# main.net
KiCad netlist of a schematic drawn in Altium Designer
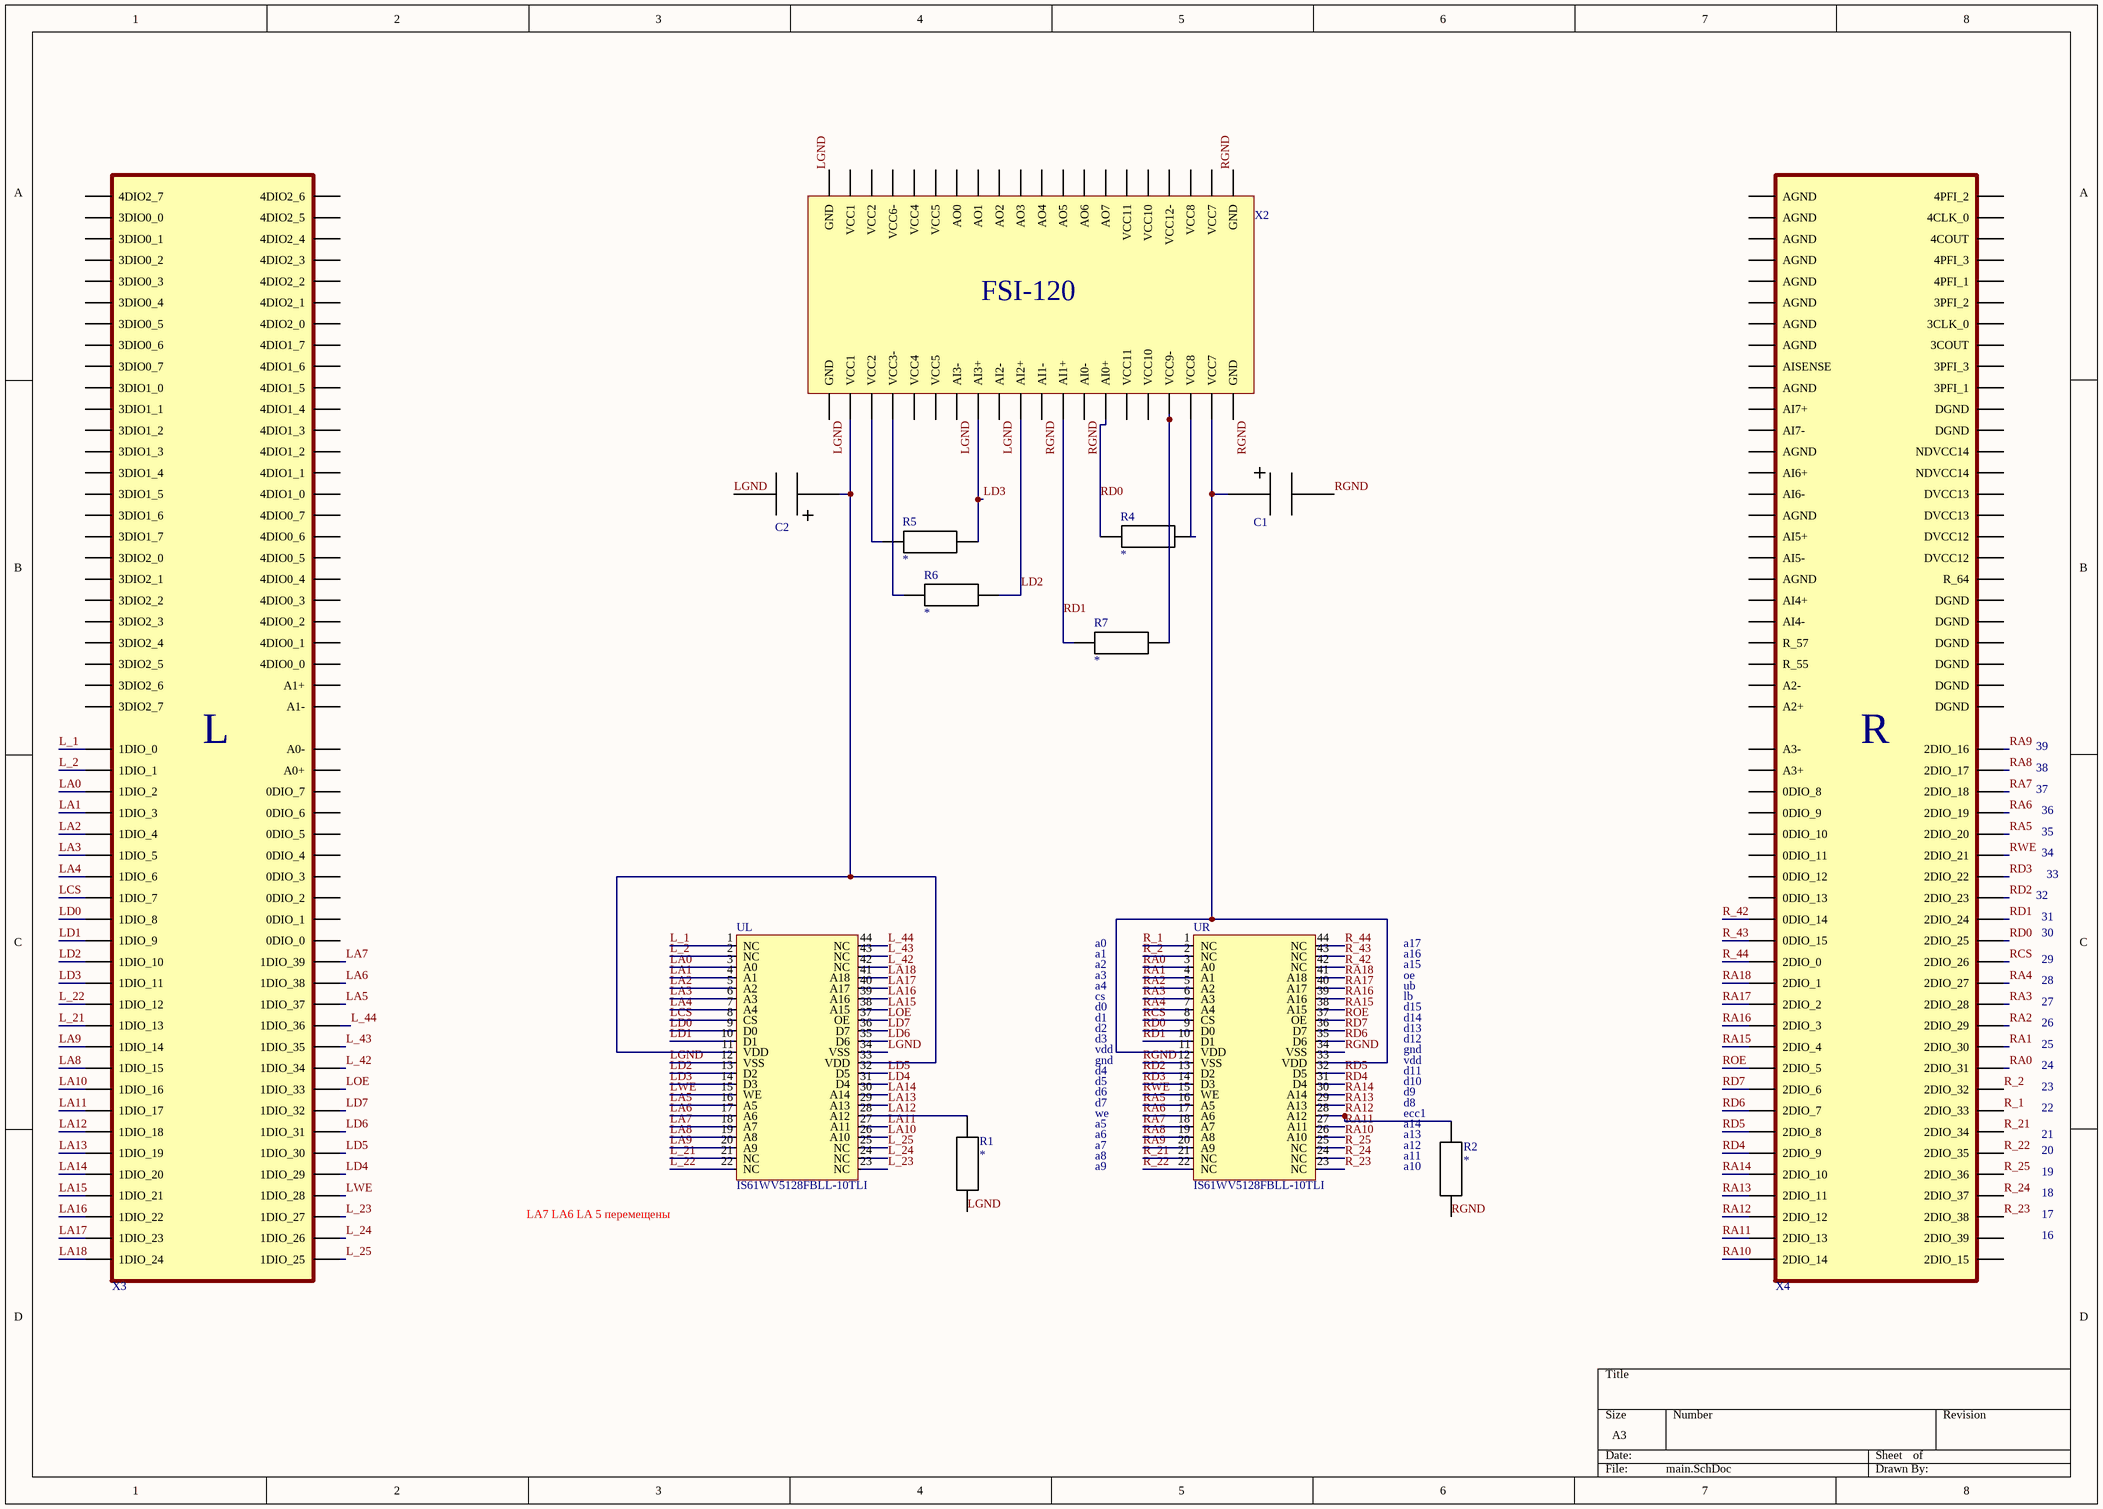
[diagram p0: main.SchDoc]

(export (version "E")
  (design (tool "Eeschema 10.0.6"))
  (components
    (comp (ref "C1")
      (value "C_Ta")
      (footprint "C_Ta")
      (description "tantalum capacitor")
      (libsource (lib "test_lib") (part "C_Ta"))
    )
    (comp (ref "C2")
      (value "C_Ta")
      (footprint "C_Ta")
      (description "tantalum capacitor")
      (libsource (lib "test_lib") (part "C_Ta"))
    )
    (comp (ref "R1")
      (value "*")
      (footprint "0805")
      (description "0805 resistor")
      (libsource (lib "test_lib") (part "R0805"))
    )
    (comp (ref "R2")
      (value "*")
      (footprint "0805")
      (description "0805 resistor")
      (libsource (lib "test_lib") (part "R0805"))
    )
    (comp (ref "R4")
      (value "*")
      (footprint "0805")
      (description "0805 resistor")
      (libsource (lib "test_lib") (part "R0805"))
    )
    (comp (ref "R5")
      (value "*")
      (footprint "0805")
      (description "0805 resistor")
      (libsource (lib "test_lib") (part "R0805"))
    )
    (comp (ref "R6")
      (value "*")
      (footprint "0805")
      (description "0805 resistor")
      (libsource (lib "test_lib") (part "R0805"))
    )
    (comp (ref "R7")
      (value "*")
      (footprint "0805")
      (description "0805 resistor")
      (libsource (lib "test_lib") (part "R0805"))
    )
    (comp (ref "UL")
      (value "IS61WV5128FBLL-10TLI")
      (footprint "TSOP (Type II)")
      (libsource (lib "test_lib") (part "IS61WV5128FBLL-10TLI"))
    )
    (comp (ref "UR")
      (value "IS61WV5128FBLL-10TLI")
      (footprint "TSOP (Type II)")
      (libsource (lib "test_lib") (part "IS61WV5128FBLL-10TLI"))
    )
    (comp (ref "X2") (value "FSI120") (footprint "FSI-120") (libsource (lib "test_lib") (part "FSI120")))
    (comp (ref "X3")
      (value "FSI-150-L")
      (footprint "FSI-150")
      (description "fsi 150 left")
      (libsource (lib "spels_lib") (part "FSI-150-L"))
    )
    (comp (ref "X4")
      (value "FSI-150-R")
      (footprint "FSI-150")
      (description "fsi 150 right")
      (libsource (lib "spels_lib") (part "FSI-150-R"))
    )
  )
  (nets
    (net (code "1") (name "/LA0") (class "Default")
      (node (ref "UL") (pin "3") (pinfunction "A0_3") (pintype "passive"))
      (node (ref "X3") (pin "R_45") (pinfunction "1DIO_2_R_45") (pintype "passive"))
    )
    (net (code "2") (name "/LA1") (class "Default")
      (node (ref "UL") (pin "4") (pinfunction "A1_4") (pintype "passive"))
      (node (ref "X3") (pin "R_43") (pinfunction "1DIO_3_R_43") (pintype "passive"))
    )
    (net (code "3") (name "/LA2") (class "Default")
      (node (ref "UL") (pin "5") (pinfunction "A2_5") (pintype "passive"))
      (node (ref "X3") (pin "R_41") (pinfunction "1DIO_4_R_41") (pintype "passive"))
    )
    (net (code "4") (name "/LA3") (class "Default")
      (node (ref "UL") (pin "6") (pinfunction "A3_6") (pintype "passive"))
      (node (ref "X3") (pin "R_39") (pinfunction "1DIO_5_R_39") (pintype "passive"))
    )
    (net (code "5") (name "/LA4") (class "Default")
      (node (ref "UL") (pin "7") (pinfunction "A4_7") (pintype "passive"))
      (node (ref "X3") (pin "R_37") (pinfunction "1DIO_6_R_37") (pintype "passive"))
    )
    (net (code "6") (name "/LA5") (class "Default")
      (node (ref "UL") (pin "16") (pinfunction "A5_16") (pintype "passive"))
      (node (ref "X3") (pin "R_26") (pinfunction "1DIO_37_R_26") (pintype "passive"))
    )
    (net (code "7") (name "/LA6") (class "Default")
      (node (ref "UL") (pin "17") (pinfunction "A6_17") (pintype "passive"))
      (node (ref "X3") (pin "R_28") (pinfunction "1DIO_38_R_28") (pintype "passive"))
    )
    (net (code "8") (name "/LA7") (class "Default")
      (node (ref "UL") (pin "18") (pinfunction "A7_18") (pintype "passive"))
      (node (ref "X3") (pin "R_30") (pinfunction "1DIO_39_R_30") (pintype "passive"))
    )
    (net (code "9") (name "/LA8") (class "Default")
      (node (ref "UL") (pin "19") (pinfunction "A8_19") (pintype "passive"))
      (node (ref "X3") (pin "R_19") (pinfunction "1DIO_15_R_19") (pintype "passive"))
    )
    (net (code "10") (name "/LA9") (class "Default")
      (node (ref "UL") (pin "20") (pinfunction "A9_20") (pintype "passive"))
      (node (ref "X3") (pin "R_21") (pinfunction "1DIO_14_R_21") (pintype "passive"))
    )
    (net (code "11") (name "/LA10") (class "Default")
      (node (ref "UL") (pin "26") (pinfunction "A10_26") (pintype "passive"))
      (node (ref "X3") (pin "R_17") (pinfunction "1DIO_16_R_17") (pintype "passive"))
    )
    (net (code "12") (name "/LA11") (class "Default")
      (node (ref "UL") (pin "27") (pinfunction "A11_27") (pintype "passive"))
      (node (ref "X3") (pin "R_15") (pinfunction "1DIO_17_R_15") (pintype "passive"))
    )
    (net (code "13") (name "/LA12") (class "Default")
      (node (ref "R1") (pin "2") (pinfunction "2_2") (pintype "passive"))
      (node (ref "UL") (pin "28") (pinfunction "A12_28") (pintype "passive"))
      (node (ref "X3") (pin "R_13") (pinfunction "1DIO_18_R_13") (pintype "passive"))
    )
    (net (code "14") (name "/LA13") (class "Default")
      (node (ref "UL") (pin "29") (pinfunction "A13_29") (pintype "passive"))
      (node (ref "X3") (pin "R_11") (pinfunction "1DIO_19_R_11") (pintype "passive"))
    )
    (net (code "15") (name "/LA14") (class "Default")
      (node (ref "UL") (pin "30") (pinfunction "A14_30") (pintype "passive"))
      (node (ref "X3") (pin "R_9") (pinfunction "1DIO_20_R_9") (pintype "passive"))
    )
    (net (code "16") (name "/LA15") (class "Default")
      (node (ref "UL") (pin "38") (pinfunction "A15_38") (pintype "passive"))
      (node (ref "X3") (pin "R_7") (pinfunction "1DIO_21_R_7") (pintype "passive"))
    )
    (net (code "17") (name "/LA16") (class "Default")
      (node (ref "UL") (pin "39") (pinfunction "A16_39") (pintype "passive"))
      (node (ref "X3") (pin "R_5") (pinfunction "1DIO_22_R_5") (pintype "passive"))
    )
    (net (code "18") (name "/LA17") (class "Default")
      (node (ref "UL") (pin "40") (pinfunction "A17_40") (pintype "passive"))
      (node (ref "X3") (pin "R_3") (pinfunction "1DIO_23_R_3") (pintype "passive"))
    )
    (net (code "19") (name "/LA18") (class "Default")
      (node (ref "UL") (pin "41") (pinfunction "A18_41") (pintype "passive"))
      (node (ref "X3") (pin "R_1") (pinfunction "1DIO_24_R_1") (pintype "passive"))
    )
    (net (code "20") (name "/LCS") (class "Default")
      (node (ref "UL") (pin "8") (pinfunction "CS_8") (pintype "passive"))
      (node (ref "X3") (pin "R_35") (pinfunction "1DIO_7_R_35") (pintype "passive"))
    )
    (net (code "21") (name "/LD0") (class "Default")
      (node (ref "UL") (pin "9") (pinfunction "D0_9") (pintype "passive"))
      (node (ref "X3") (pin "R_33") (pinfunction "1DIO_8_R_33") (pintype "passive"))
    )
    (net (code "22") (name "/LD1") (class "Default")
      (node (ref "UL") (pin "10") (pinfunction "D1_10") (pintype "passive"))
      (node (ref "X3") (pin "R_31") (pinfunction "1DIO_9_R_31") (pintype "passive"))
    )
    (net (code "23") (name "/LD2") (class "Default")
      (node (ref "R6") (pin "2") (pinfunction "2_2") (pintype "passive"))
      (node (ref "UL") (pin "13") (pinfunction "D2_13") (pintype "passive"))
      (node (ref "X2") (pin "11") (pinfunction "AI2+_11") (pintype "passive"))
      (node (ref "X3") (pin "R_29") (pinfunction "1DIO_10_R_29") (pintype "passive"))
    )
    (net (code "24") (name "/LD3") (class "Default")
      (node (ref "R5") (pin "2") (pinfunction "2_2") (pintype "passive"))
      (node (ref "UL") (pin "14") (pinfunction "D3_14") (pintype "passive"))
      (node (ref "X2") (pin "13") (pinfunction "AI3+_13") (pintype "passive"))
      (node (ref "X3") (pin "R_27") (pinfunction "1DIO_11_R_27") (pintype "passive"))
    )
    (net (code "25") (name "/LD4") (class "Default")
      (node (ref "UL") (pin "31") (pinfunction "D4_31") (pintype "passive"))
      (node (ref "X3") (pin "R_10") (pinfunction "1DIO_29_R_10") (pintype "passive"))
    )
    (net (code "26") (name "/LD5") (class "Default")
      (node (ref "UL") (pin "32") (pinfunction "D5_32") (pintype "passive"))
      (node (ref "X3") (pin "R_12") (pinfunction "1DIO_30_R_12") (pintype "passive"))
    )
    (net (code "27") (name "/LD6") (class "Default")
      (node (ref "UL") (pin "35") (pinfunction "D6_35") (pintype "passive"))
      (node (ref "X3") (pin "R_14") (pinfunction "1DIO_31_R_14") (pintype "passive"))
    )
    (net (code "28") (name "/LD7") (class "Default")
      (node (ref "UL") (pin "36") (pinfunction "D7_36") (pintype "passive"))
      (node (ref "X3") (pin "R_16") (pinfunction "1DIO_32_R_16") (pintype "passive"))
    )
    (net (code "29") (name "/LGND") (class "Default")
      (node (ref "C2") (pin "2") (pinfunction "2_2") (pintype "passive"))
      (node (ref "R1") (pin "1") (pinfunction "1_1") (pintype "passive"))
      (node (ref "UL") (pin "12") (pinfunction "VSS_12") (pintype "passive"))
      (node (ref "UL") (pin "34") (pinfunction "VSS_34") (pintype "passive"))
      (node (ref "X2") (pin "12") (pinfunction "AI2-_12") (pintype "passive"))
      (node (ref "X2") (pin "14") (pinfunction "AI3-_14") (pintype "passive"))
      (node (ref "X2") (pin "20") (pinfunction "GND_20") (pintype "passive"))
      (node (ref "X2") (pin "21") (pinfunction "GND_21") (pintype "passive"))
    )
    (net (code "30") (name "/LOE") (class "Default")
      (node (ref "UL") (pin "37") (pinfunction "OE_37") (pintype "passive"))
      (node (ref "X3") (pin "R_18") (pinfunction "1DIO_33_R_18") (pintype "passive"))
    )
    (net (code "31") (name "/LWE") (class "Default")
      (node (ref "UL") (pin "15") (pinfunction "WE_15") (pintype "passive"))
      (node (ref "X3") (pin "R_8") (pinfunction "1DIO_28_R_8") (pintype "passive"))
    )
    (net (code "32") (name "/L_1") (class "Default")
      (node (ref "UL") (pin "1") (pinfunction "NC_1") (pintype "passive"))
      (node (ref "X3") (pin "R_49") (pinfunction "1DIO_0_R_49") (pintype "passive"))
    )
    (net (code "33") (name "/L_2") (class "Default")
      (node (ref "UL") (pin "2") (pinfunction "NC_2") (pintype "passive"))
      (node (ref "X3") (pin "R_47") (pinfunction "1DIO_1_R_47") (pintype "passive"))
    )
    (net (code "34") (name "/L_21") (class "Default")
      (node (ref "UL") (pin "21") (pinfunction "NC_21") (pintype "passive"))
      (node (ref "X3") (pin "R_23") (pinfunction "1DIO_13_R_23") (pintype "passive"))
    )
    (net (code "35") (name "/L_22") (class "Default")
      (node (ref "UL") (pin "22") (pinfunction "NC_22") (pintype "passive"))
      (node (ref "X3") (pin "R_25") (pinfunction "1DIO_12_R_25") (pintype "passive"))
    )
    (net (code "36") (name "/L_23") (class "Default")
      (node (ref "UL") (pin "23") (pinfunction "NC_23") (pintype "passive"))
      (node (ref "X3") (pin "R_6") (pinfunction "1DIO_27_R_6") (pintype "passive"))
    )
    (net (code "37") (name "/L_24") (class "Default")
      (node (ref "UL") (pin "24") (pinfunction "NC_24") (pintype "passive"))
      (node (ref "X3") (pin "R_4") (pinfunction "1DIO_26_R_4") (pintype "passive"))
    )
    (net (code "38") (name "/L_25") (class "Default")
      (node (ref "UL") (pin "25") (pinfunction "NC_25") (pintype "passive"))
      (node (ref "X3") (pin "R_2") (pinfunction "1DIO_25_R_2") (pintype "passive"))
    )
    (net (code "39") (name "/L_42") (class "Default")
      (node (ref "UL") (pin "42") (pinfunction "NC_42") (pintype "passive"))
      (node (ref "X3") (pin "R_20") (pinfunction "1DIO_34_R_20") (pintype "passive"))
    )
    (net (code "40") (name "/L_43") (class "Default")
      (node (ref "UL") (pin "43") (pinfunction "NC_43") (pintype "passive"))
      (node (ref "X3") (pin "R_22") (pinfunction "1DIO_35_R_22") (pintype "passive"))
    )
    (net (code "41") (name "/L_44") (class "Default")
      (node (ref "UL") (pin "44") (pinfunction "NC_44") (pintype "passive"))
      (node (ref "X3") (pin "R_24") (pinfunction "1DIO_36_R_24") (pintype "passive"))
    )
    (net (code "42") (name "/RA0") (class "Default")
      (node (ref "UR") (pin "3") (pinfunction "A0_3") (pintype "passive"))
      (node (ref "X4") (pin "R_20") (pinfunction "2DIO_31_R_20") (pintype "passive"))
    )
    (net (code "43") (name "/RA1") (class "Default")
      (node (ref "UR") (pin "4") (pinfunction "A1_4") (pintype "passive"))
      (node (ref "X4") (pin "R_22") (pinfunction "2DIO_30_R_22") (pintype "passive"))
    )
    (net (code "44") (name "/RA2") (class "Default")
      (node (ref "UR") (pin "5") (pinfunction "A2_5") (pintype "passive"))
      (node (ref "X4") (pin "R_24") (pinfunction "2DIO_29_R_24") (pintype "passive"))
    )
    (net (code "45") (name "/RA3") (class "Default")
      (node (ref "UR") (pin "6") (pinfunction "A3_6") (pintype "passive"))
      (node (ref "X4") (pin "R_26") (pinfunction "2DIO_28_R_26") (pintype "passive"))
    )
    (net (code "46") (name "/RA4") (class "Default")
      (node (ref "UR") (pin "7") (pinfunction "A4_7") (pintype "passive"))
      (node (ref "X4") (pin "R_28") (pinfunction "2DIO_27_R_28") (pintype "passive"))
    )
    (net (code "47") (name "/RA5") (class "Default")
      (node (ref "UR") (pin "16") (pinfunction "A5_16") (pintype "passive"))
      (node (ref "X4") (pin "R_42") (pinfunction "2DIO_20_R_42") (pintype "passive"))
    )
    (net (code "48") (name "/RA6") (class "Default")
      (node (ref "UR") (pin "17") (pinfunction "A6_17") (pintype "passive"))
      (node (ref "X4") (pin "R_44") (pinfunction "2DIO_19_R_44") (pintype "passive"))
    )
    (net (code "49") (name "/RA7") (class "Default")
      (node (ref "UR") (pin "18") (pinfunction "A7_18") (pintype "passive"))
      (node (ref "X4") (pin "R_46") (pinfunction "2DIO_18_R_46") (pintype "passive"))
    )
    (net (code "50") (name "/RA8") (class "Default")
      (node (ref "UR") (pin "19") (pinfunction "A8_19") (pintype "passive"))
      (node (ref "X4") (pin "R_48") (pinfunction "2DIO_17_R_48") (pintype "passive"))
    )
    (net (code "51") (name "/RA9") (class "Default")
      (node (ref "UR") (pin "20") (pinfunction "A9_20") (pintype "passive"))
      (node (ref "X4") (pin "R_50") (pinfunction "2DIO_16_R_50") (pintype "passive"))
    )
    (net (code "52") (name "/RA10") (class "Default")
      (node (ref "UR") (pin "26") (pinfunction "A10_26") (pintype "passive"))
      (node (ref "X4") (pin "R_1") (pinfunction "2DIO_14_R_1") (pintype "passive"))
    )
    (net (code "53") (name "/RA11") (class "Default")
      (node (ref "UR") (pin "27") (pinfunction "A11_27") (pintype "passive"))
      (node (ref "X4") (pin "R_3") (pinfunction "2DIO_13_R_3") (pintype "passive"))
    )
    (net (code "54") (name "/RA12") (class "Default")
      (node (ref "R2") (pin "2") (pinfunction "2_2") (pintype "passive"))
      (node (ref "UR") (pin "28") (pinfunction "A12_28") (pintype "passive"))
      (node (ref "X4") (pin "R_5") (pinfunction "2DIO_12_R_5") (pintype "passive"))
    )
    (net (code "55") (name "/RA13") (class "Default")
      (node (ref "UR") (pin "29") (pinfunction "A13_29") (pintype "passive"))
      (node (ref "X4") (pin "R_7") (pinfunction "2DIO_11_R_7") (pintype "passive"))
    )
    (net (code "56") (name "/RA14") (class "Default")
      (node (ref "UR") (pin "30") (pinfunction "A14_30") (pintype "passive"))
      (node (ref "X4") (pin "R_9") (pinfunction "2DIO_10_R_9") (pintype "passive"))
    )
    (net (code "57") (name "/RA15") (class "Default")
      (node (ref "UR") (pin "38") (pinfunction "A15_38") (pintype "passive"))
      (node (ref "X4") (pin "R_21") (pinfunction "2DIO_4_R_21") (pintype "passive"))
    )
    (net (code "58") (name "/RA16") (class "Default")
      (node (ref "UR") (pin "39") (pinfunction "A16_39") (pintype "passive"))
      (node (ref "X4") (pin "R_23") (pinfunction "2DIO_3_R_23") (pintype "passive"))
    )
    (net (code "59") (name "/RA17") (class "Default")
      (node (ref "UR") (pin "40") (pinfunction "A17_40") (pintype "passive"))
      (node (ref "X4") (pin "R_25") (pinfunction "2DIO_2_R_25") (pintype "passive"))
    )
    (net (code "60") (name "/RA18") (class "Default")
      (node (ref "UR") (pin "41") (pinfunction "A18_41") (pintype "passive"))
      (node (ref "X4") (pin "R_27") (pinfunction "2DIO_1_R_27") (pintype "passive"))
    )
    (net (code "61") (name "/RCS") (class "Default")
      (node (ref "UR") (pin "8") (pinfunction "CS_8") (pintype "passive"))
      (node (ref "X4") (pin "R_30") (pinfunction "2DIO_26_R_30") (pintype "passive"))
    )
    (net (code "62") (name "/RD0") (class "Default")
      (node (ref "R4") (pin "1") (pinfunction "1_1") (pintype "passive"))
      (node (ref "UR") (pin "9") (pinfunction "D0_9") (pintype "passive"))
      (node (ref "X2") (pin "7") (pinfunction "AI0+_7") (pintype "passive"))
      (node (ref "X4") (pin "R_32") (pinfunction "2DIO_25_R_32") (pintype "passive"))
    )
    (net (code "63") (name "/RD1") (class "Default")
      (node (ref "R7") (pin "1") (pinfunction "1_1") (pintype "passive"))
      (node (ref "UR") (pin "10") (pinfunction "D1_10") (pintype "passive"))
      (node (ref "X2") (pin "9") (pinfunction "AI1+_9") (pintype "passive"))
      (node (ref "X4") (pin "R_34") (pinfunction "2DIO_24_R_34") (pintype "passive"))
    )
    (net (code "64") (name "/RD2") (class "Default")
      (node (ref "UR") (pin "13") (pinfunction "D2_13") (pintype "passive"))
      (node (ref "X4") (pin "R_36") (pinfunction "2DIO_23_R_36") (pintype "passive"))
    )
    (net (code "65") (name "/RD3") (class "Default")
      (node (ref "UR") (pin "14") (pinfunction "D3_14") (pintype "passive"))
      (node (ref "X4") (pin "R_38") (pinfunction "2DIO_22_R_38") (pintype "passive"))
    )
    (net (code "66") (name "/RD4") (class "Default")
      (node (ref "UR") (pin "31") (pinfunction "D4_31") (pintype "passive"))
      (node (ref "X4") (pin "R_11") (pinfunction "2DIO_9_R_11") (pintype "passive"))
    )
    (net (code "67") (name "/RD5") (class "Default")
      (node (ref "UR") (pin "32") (pinfunction "D5_32") (pintype "passive"))
      (node (ref "X4") (pin "R_13") (pinfunction "2DIO_8_R_13") (pintype "passive"))
    )
    (net (code "68") (name "/RD6") (class "Default")
      (node (ref "UR") (pin "35") (pinfunction "D6_35") (pintype "passive"))
      (node (ref "X4") (pin "R_15") (pinfunction "2DIO_7_R_15") (pintype "passive"))
    )
    (net (code "69") (name "/RD7") (class "Default")
      (node (ref "UR") (pin "36") (pinfunction "D7_36") (pintype "passive"))
      (node (ref "X4") (pin "R_17") (pinfunction "2DIO_6_R_17") (pintype "passive"))
    )
    (net (code "70") (name "/RGND") (class "Default")
      (node (ref "C1") (pin "2") (pinfunction "2_2") (pintype "passive"))
      (node (ref "R2") (pin "1") (pinfunction "1_1") (pintype "passive"))
      (node (ref "UR") (pin "12") (pinfunction "VSS_12") (pintype "passive"))
      (node (ref "UR") (pin "34") (pinfunction "VSS_34") (pintype "passive"))
      (node (ref "X2") (pin "1") (pinfunction "GND_1") (pintype "passive"))
      (node (ref "X2") (pin "10") (pinfunction "AI1-_10") (pintype "passive"))
      (node (ref "X2") (pin "40") (pinfunction "GND_40") (pintype "passive"))
      (node (ref "X2") (pin "8") (pinfunction "AI0-_8") (pintype "passive"))
    )
    (net (code "71") (name "/ROE") (class "Default")
      (node (ref "UR") (pin "37") (pinfunction "OE_37") (pintype "passive"))
      (node (ref "X4") (pin "R_19") (pinfunction "2DIO_5_R_19") (pintype "passive"))
    )
    (net (code "72") (name "/RWE") (class "Default")
      (node (ref "UR") (pin "15") (pinfunction "WE_15") (pintype "passive"))
      (node (ref "X4") (pin "R_40") (pinfunction "2DIO_21_R_40") (pintype "passive"))
    )
    (net (code "73") (name "/R_1") (class "Default")
      (node (ref "UR") (pin "1") (pinfunction "NC_1") (pintype "passive"))
      (node (ref "X4") (pin "R_16") (pinfunction "2DIO_33_R_16") (pintype "passive"))
    )
    (net (code "74") (name "/R_2") (class "Default")
      (node (ref "UR") (pin "2") (pinfunction "NC_2") (pintype "passive"))
      (node (ref "X4") (pin "R_18") (pinfunction "2DIO_32_R_18") (pintype "passive"))
    )
    (net (code "75") (name "/R_21") (class "Default")
      (node (ref "UR") (pin "21") (pinfunction "NC_21") (pintype "passive"))
      (node (ref "X4") (pin "R_14") (pinfunction "2DIO_34_R_14") (pintype "passive"))
    )
    (net (code "76") (name "/R_22") (class "Default")
      (node (ref "UR") (pin "22") (pinfunction "NC_22") (pintype "passive"))
      (node (ref "X4") (pin "R_12") (pinfunction "2DIO_35_R_12") (pintype "passive"))
    )
    (net (code "77") (name "/R_23") (class "Default")
      (node (ref "UR") (pin "23") (pinfunction "NC_23") (pintype "passive"))
      (node (ref "X4") (pin "R_6") (pinfunction "2DIO_38_R_6") (pintype "passive"))
    )
    (net (code "78") (name "/R_24") (class "Default")
      (node (ref "UR") (pin "24") (pinfunction "NC_24") (pintype "passive"))
      (node (ref "X4") (pin "R_8") (pinfunction "2DIO_37_R_8") (pintype "passive"))
    )
    (net (code "79") (name "/R_25") (class "Default")
      (node (ref "UR") (pin "25") (pinfunction "NC_25") (pintype "passive"))
      (node (ref "X4") (pin "R_10") (pinfunction "2DIO_36_R_10") (pintype "passive"))
    )
    (net (code "80") (name "/R_42") (class "Default")
      (node (ref "UR") (pin "42") (pinfunction "NC_42") (pintype "passive"))
      (node (ref "X4") (pin "R_33") (pinfunction "0DIO_14_R_33") (pintype "passive"))
    )
    (net (code "81") (name "/R_43") (class "Default")
      (node (ref "UR") (pin "43") (pinfunction "NC_43") (pintype "passive"))
      (node (ref "X4") (pin "R_31") (pinfunction "0DIO_15_R_31") (pintype "passive"))
    )
    (net (code "82") (name "/R_44") (class "Default")
      (node (ref "UR") (pin "44") (pinfunction "NC_44") (pintype "passive"))
      (node (ref "X4") (pin "R_29") (pinfunction "2DIO_0_R_29") (pintype "passive"))
    )
    (net (code "83") (name "Net-(C1-Pad1)") (class "Default")
      (node (ref "C1") (pin "1") (pinfunction "1_1") (pintype "passive"))
      (node (ref "UR") (pin "11") (pinfunction "VDD_11") (pintype "passive"))
      (node (ref "UR") (pin "33") (pinfunction "VDD_33") (pintype "passive"))
      (node (ref "X2") (pin "2") (pinfunction "VCC7_2") (pintype "passive"))
    )
    (net (code "84") (name "Net-(C2-Pad1)") (class "Default")
      (node (ref "C2") (pin "1") (pinfunction "1_1") (pintype "passive"))
      (node (ref "UL") (pin "11") (pinfunction "VDD_11") (pintype "passive"))
      (node (ref "UL") (pin "33") (pinfunction "VDD_33") (pintype "passive"))
      (node (ref "X2") (pin "19") (pinfunction "VCC1_19") (pintype "passive"))
    )
    (net (code "85") (name "Net-(R4-Pad2)") (class "Default")
      (node (ref "R4") (pin "2") (pinfunction "2_2") (pintype "passive"))
      (node (ref "X2") (pin "3") (pinfunction "VCC8_3") (pintype "passive"))
    )
    (net (code "86") (name "Net-(R5-Pad1)") (class "Default")
      (node (ref "R5") (pin "1") (pinfunction "1_1") (pintype "passive"))
      (node (ref "X2") (pin "18") (pinfunction "VCC2_18") (pintype "passive"))
    )
    (net (code "87") (name "Net-(X2-VCC3-)") (class "Default")
      (node (ref "R6") (pin "1") (pinfunction "1_1") (pintype "passive"))
      (node (ref "X2") (pin "17") (pinfunction "VCC3-_17") (pintype "passive"))
    )
    (net (code "88") (name "Net-(X2-VCC9-)") (class "Default")
      (node (ref "R7") (pin "2") (pinfunction "2_2") (pintype "passive"))
      (node (ref "X2") (pin "4") (pinfunction "VCC9-_4") (pintype "passive"))
    )
    (net (code "89") (name "unconnected-(X2-AO0-Pad27)") (class "Default")
      (node (ref "X2") (pin "27") (pinfunction "AO0_27") (pintype "passive"))
    )
    (net (code "90") (name "unconnected-(X2-AO1-Pad28)") (class "Default")
      (node (ref "X2") (pin "28") (pinfunction "AO1_28") (pintype "passive"))
    )
    (net (code "91") (name "unconnected-(X2-AO2-Pad29)") (class "Default")
      (node (ref "X2") (pin "29") (pinfunction "AO2_29") (pintype "passive"))
    )
    (net (code "92") (name "unconnected-(X2-AO3-Pad30)") (class "Default")
      (node (ref "X2") (pin "30") (pinfunction "AO3_30") (pintype "passive"))
    )
    (net (code "93") (name "unconnected-(X2-AO4-Pad31)") (class "Default")
      (node (ref "X2") (pin "31") (pinfunction "AO4_31") (pintype "passive"))
    )
    (net (code "94") (name "unconnected-(X2-AO5-Pad32)") (class "Default")
      (node (ref "X2") (pin "32") (pinfunction "AO5_32") (pintype "passive"))
    )
    (net (code "95") (name "unconnected-(X2-AO6-Pad33)") (class "Default")
      (node (ref "X2") (pin "33") (pinfunction "AO6_33") (pintype "passive"))
    )
    (net (code "96") (name "unconnected-(X2-AO7-Pad34)") (class "Default")
      (node (ref "X2") (pin "34") (pinfunction "AO7_34") (pintype "passive"))
    )
    (net (code "97") (name "unconnected-(X2-VCC1-Pad22)") (class "Default")
      (node (ref "X2") (pin "22") (pinfunction "VCC1_22") (pintype "passive"))
    )
    (net (code "98") (name "unconnected-(X2-VCC2-Pad23)") (class "Default")
      (node (ref "X2") (pin "23") (pinfunction "VCC2_23") (pintype "passive"))
    )
    (net (code "99") (name "unconnected-(X2-VCC4-Pad16)") (class "Default")
      (node (ref "X2") (pin "16") (pinfunction "VCC4_16") (pintype "passive"))
    )
    (net (code "100") (name "unconnected-(X2-VCC4-Pad25)") (class "Default")
      (node (ref "X2") (pin "25") (pinfunction "VCC4_25") (pintype "passive"))
    )
    (net (code "101") (name "unconnected-(X2-VCC5-Pad15)") (class "Default")
      (node (ref "X2") (pin "15") (pinfunction "VCC5_15") (pintype "passive"))
    )
    (net (code "102") (name "unconnected-(X2-VCC5-Pad26)") (class "Default")
      (node (ref "X2") (pin "26") (pinfunction "VCC5_26") (pintype "passive"))
    )
    (net (code "103") (name "unconnected-(X2-VCC6--Pad24)") (class "Default")
      (node (ref "X2") (pin "24") (pinfunction "VCC6-_24") (pintype "passive"))
    )
    (net (code "104") (name "unconnected-(X2-VCC7-Pad37)") (class "Default")
      (node (ref "X2") (pin "37") (pinfunction "VCC7_37") (pintype "passive"))
    )
    (net (code "105") (name "unconnected-(X2-VCC8-Pad38)") (class "Default")
      (node (ref "X2") (pin "38") (pinfunction "VCC8_38") (pintype "passive"))
    )
    (net (code "106") (name "unconnected-(X2-VCC10-Pad5)") (class "Default")
      (node (ref "X2") (pin "5") (pinfunction "VCC10_5") (pintype "passive"))
    )
    (net (code "107") (name "unconnected-(X2-VCC10-Pad36)") (class "Default")
      (node (ref "X2") (pin "36") (pinfunction "VCC10_36") (pintype "passive"))
    )
    (net (code "108") (name "unconnected-(X2-VCC11-Pad6)") (class "Default")
      (node (ref "X2") (pin "6") (pinfunction "VCC11_6") (pintype "passive"))
    )
    (net (code "109") (name "unconnected-(X2-VCC11-Pad35)") (class "Default")
      (node (ref "X2") (pin "35") (pinfunction "VCC11_35") (pintype "passive"))
    )
    (net (code "110") (name "unconnected-(X2-VCC12--Pad39)") (class "Default")
      (node (ref "X2") (pin "39") (pinfunction "VCC12-_39") (pintype "passive"))
    )
    (net (code "111") (name "unconnected-(X3-0DIO_0-PadR_32)") (class "Default")
      (node (ref "X3") (pin "R_32") (pinfunction "0DIO_0_R_32") (pintype "passive"))
    )
    (net (code "112") (name "unconnected-(X3-0DIO_1-PadR_34)") (class "Default")
      (node (ref "X3") (pin "R_34") (pinfunction "0DIO_1_R_34") (pintype "passive"))
    )
    (net (code "113") (name "unconnected-(X3-0DIO_2-PadR_36)") (class "Default")
      (node (ref "X3") (pin "R_36") (pinfunction "0DIO_2_R_36") (pintype "passive"))
    )
    (net (code "114") (name "unconnected-(X3-0DIO_3-PadR_38)") (class "Default")
      (node (ref "X3") (pin "R_38") (pinfunction "0DIO_3_R_38") (pintype "passive"))
    )
    (net (code "115") (name "unconnected-(X3-0DIO_4-PadR_40)") (class "Default")
      (node (ref "X3") (pin "R_40") (pinfunction "0DIO_4_R_40") (pintype "passive"))
    )
    (net (code "116") (name "unconnected-(X3-0DIO_5-PadR_42)") (class "Default")
      (node (ref "X3") (pin "R_42") (pinfunction "0DIO_5_R_42") (pintype "passive"))
    )
    (net (code "117") (name "unconnected-(X3-0DIO_6-PadR_44)") (class "Default")
      (node (ref "X3") (pin "R_44") (pinfunction "0DIO_6_R_44") (pintype "passive"))
    )
    (net (code "118") (name "unconnected-(X3-0DIO_7-PadR_46)") (class "Default")
      (node (ref "X3") (pin "R_46") (pinfunction "0DIO_7_R_46") (pintype "passive"))
    )
    (net (code "119") (name "unconnected-(X3-3DIO0_0-PadR_97)") (class "Default")
      (node (ref "X3") (pin "R_97") (pinfunction "3DIO0_0_R_97") (pintype "passive"))
    )
    (net (code "120") (name "unconnected-(X3-3DIO0_1-PadR_95)") (class "Default")
      (node (ref "X3") (pin "R_95") (pinfunction "3DIO0_1_R_95") (pintype "passive"))
    )
    (net (code "121") (name "unconnected-(X3-3DIO0_2-PadR_93)") (class "Default")
      (node (ref "X3") (pin "R_93") (pinfunction "3DIO0_2_R_93") (pintype "passive"))
    )
    (net (code "122") (name "unconnected-(X3-3DIO0_3-PadR_91)") (class "Default")
      (node (ref "X3") (pin "R_91") (pinfunction "3DIO0_3_R_91") (pintype "passive"))
    )
    (net (code "123") (name "unconnected-(X3-3DIO0_4-PadR_89)") (class "Default")
      (node (ref "X3") (pin "R_89") (pinfunction "3DIO0_4_R_89") (pintype "passive"))
    )
    (net (code "124") (name "unconnected-(X3-3DIO0_5-PadR_87)") (class "Default")
      (node (ref "X3") (pin "R_87") (pinfunction "3DIO0_5_R_87") (pintype "passive"))
    )
    (net (code "125") (name "unconnected-(X3-3DIO0_6-PadR_85)") (class "Default")
      (node (ref "X3") (pin "R_85") (pinfunction "3DIO0_6_R_85") (pintype "passive"))
    )
    (net (code "126") (name "unconnected-(X3-3DIO0_7-PadR_83)") (class "Default")
      (node (ref "X3") (pin "R_83") (pinfunction "3DIO0_7_R_83") (pintype "passive"))
    )
    (net (code "127") (name "unconnected-(X3-3DIO1_0-PadR_81)") (class "Default")
      (node (ref "X3") (pin "R_81") (pinfunction "3DIO1_0_R_81") (pintype "passive"))
    )
    (net (code "128") (name "unconnected-(X3-3DIO1_1-PadR_79)") (class "Default")
      (node (ref "X3") (pin "R_79") (pinfunction "3DIO1_1_R_79") (pintype "passive"))
    )
    (net (code "129") (name "unconnected-(X3-3DIO1_2-PadR_77)") (class "Default")
      (node (ref "X3") (pin "R_77") (pinfunction "3DIO1_2_R_77") (pintype "passive"))
    )
    (net (code "130") (name "unconnected-(X3-3DIO1_3-PadR_75)") (class "Default")
      (node (ref "X3") (pin "R_75") (pinfunction "3DIO1_3_R_75") (pintype "passive"))
    )
    (net (code "131") (name "unconnected-(X3-3DIO1_4-PadR_73)") (class "Default")
      (node (ref "X3") (pin "R_73") (pinfunction "3DIO1_4_R_73") (pintype "passive"))
    )
    (net (code "132") (name "unconnected-(X3-3DIO1_5-PadR_71)") (class "Default")
      (node (ref "X3") (pin "R_71") (pinfunction "3DIO1_5_R_71") (pintype "passive"))
    )
    (net (code "133") (name "unconnected-(X3-3DIO1_6-PadR_69)") (class "Default")
      (node (ref "X3") (pin "R_69") (pinfunction "3DIO1_6_R_69") (pintype "passive"))
    )
    (net (code "134") (name "unconnected-(X3-3DIO1_7-PadR_67)") (class "Default")
      (node (ref "X3") (pin "R_67") (pinfunction "3DIO1_7_R_67") (pintype "passive"))
    )
    (net (code "135") (name "unconnected-(X3-3DIO2_0-PadR_65)") (class "Default")
      (node (ref "X3") (pin "R_65") (pinfunction "3DIO2_0_R_65") (pintype "passive"))
    )
    (net (code "136") (name "unconnected-(X3-3DIO2_1-PadR_63)") (class "Default")
      (node (ref "X3") (pin "R_63") (pinfunction "3DIO2_1_R_63") (pintype "passive"))
    )
    (net (code "137") (name "unconnected-(X3-3DIO2_2-PadR_61)") (class "Default")
      (node (ref "X3") (pin "R_61") (pinfunction "3DIO2_2_R_61") (pintype "passive"))
    )
    (net (code "138") (name "unconnected-(X3-3DIO2_3-PadR_59)") (class "Default")
      (node (ref "X3") (pin "R_59") (pinfunction "3DIO2_3_R_59") (pintype "passive"))
    )
    (net (code "139") (name "unconnected-(X3-3DIO2_4-PadR_57)") (class "Default")
      (node (ref "X3") (pin "R_57") (pinfunction "3DIO2_4_R_57") (pintype "passive"))
    )
    (net (code "140") (name "unconnected-(X3-3DIO2_5-PadR_55)") (class "Default")
      (node (ref "X3") (pin "R_55") (pinfunction "3DIO2_5_R_55") (pintype "passive"))
    )
    (net (code "141") (name "unconnected-(X3-3DIO2_6-PadR_53)") (class "Default")
      (node (ref "X3") (pin "R_53") (pinfunction "3DIO2_6_R_53") (pintype "passive"))
    )
    (net (code "142") (name "unconnected-(X3-3DIO2_7-PadR_51)") (class "Default")
      (node (ref "X3") (pin "R_51") (pinfunction "3DIO2_7_R_51") (pintype "passive"))
    )
    (net (code "143") (name "unconnected-(X3-4DIO0_0-PadR_56)") (class "Default")
      (node (ref "X3") (pin "R_56") (pinfunction "4DIO0_0_R_56") (pintype "passive"))
    )
    (net (code "144") (name "unconnected-(X3-4DIO0_1-PadR_58)") (class "Default")
      (node (ref "X3") (pin "R_58") (pinfunction "4DIO0_1_R_58") (pintype "passive"))
    )
    (net (code "145") (name "unconnected-(X3-4DIO0_2-PadR_60)") (class "Default")
      (node (ref "X3") (pin "R_60") (pinfunction "4DIO0_2_R_60") (pintype "passive"))
    )
    (net (code "146") (name "unconnected-(X3-4DIO0_3-PadR_62)") (class "Default")
      (node (ref "X3") (pin "R_62") (pinfunction "4DIO0_3_R_62") (pintype "passive"))
    )
    (net (code "147") (name "unconnected-(X3-4DIO0_4-PadR_64)") (class "Default")
      (node (ref "X3") (pin "R_64") (pinfunction "4DIO0_4_R_64") (pintype "passive"))
    )
    (net (code "148") (name "unconnected-(X3-4DIO0_5-PadR_66)") (class "Default")
      (node (ref "X3") (pin "R_66") (pinfunction "4DIO0_5_R_66") (pintype "passive"))
    )
    (net (code "149") (name "unconnected-(X3-4DIO0_6-PadR_68)") (class "Default")
      (node (ref "X3") (pin "R_68") (pinfunction "4DIO0_6_R_68") (pintype "passive"))
    )
    (net (code "150") (name "unconnected-(X3-4DIO0_7-PadR_70)") (class "Default")
      (node (ref "X3") (pin "R_70") (pinfunction "4DIO0_7_R_70") (pintype "passive"))
    )
    (net (code "151") (name "unconnected-(X3-4DIO1_0-PadR_72)") (class "Default")
      (node (ref "X3") (pin "R_72") (pinfunction "4DIO1_0_R_72") (pintype "passive"))
    )
    (net (code "152") (name "unconnected-(X3-4DIO1_1-PadR_74)") (class "Default")
      (node (ref "X3") (pin "R_74") (pinfunction "4DIO1_1_R_74") (pintype "passive"))
    )
    (net (code "153") (name "unconnected-(X3-4DIO1_2-PadR_76)") (class "Default")
      (node (ref "X3") (pin "R_76") (pinfunction "4DIO1_2_R_76") (pintype "passive"))
    )
    (net (code "154") (name "unconnected-(X3-4DIO1_3-PadR_78)") (class "Default")
      (node (ref "X3") (pin "R_78") (pinfunction "4DIO1_3_R_78") (pintype "passive"))
    )
    (net (code "155") (name "unconnected-(X3-4DIO1_4-PadR_80)") (class "Default")
      (node (ref "X3") (pin "R_80") (pinfunction "4DIO1_4_R_80") (pintype "passive"))
    )
    (net (code "156") (name "unconnected-(X3-4DIO1_5-PadR_82)") (class "Default")
      (node (ref "X3") (pin "R_82") (pinfunction "4DIO1_5_R_82") (pintype "passive"))
    )
    (net (code "157") (name "unconnected-(X3-4DIO1_6-PadR_84)") (class "Default")
      (node (ref "X3") (pin "R_84") (pinfunction "4DIO1_6_R_84") (pintype "passive"))
    )
    (net (code "158") (name "unconnected-(X3-4DIO1_7-PadR_86)") (class "Default")
      (node (ref "X3") (pin "R_86") (pinfunction "4DIO1_7_R_86") (pintype "passive"))
    )
    (net (code "159") (name "unconnected-(X3-4DIO2_0-PadR_88)") (class "Default")
      (node (ref "X3") (pin "R_88") (pinfunction "4DIO2_0_R_88") (pintype "passive"))
    )
    (net (code "160") (name "unconnected-(X3-4DIO2_1-PadR_90)") (class "Default")
      (node (ref "X3") (pin "R_90") (pinfunction "4DIO2_1_R_90") (pintype "passive"))
    )
    (net (code "161") (name "unconnected-(X3-4DIO2_2-PadR_92)") (class "Default")
      (node (ref "X3") (pin "R_92") (pinfunction "4DIO2_2_R_92") (pintype "passive"))
    )
    (net (code "162") (name "unconnected-(X3-4DIO2_3-PadR_94)") (class "Default")
      (node (ref "X3") (pin "R_94") (pinfunction "4DIO2_3_R_94") (pintype "passive"))
    )
    (net (code "163") (name "unconnected-(X3-4DIO2_4-PadR_96)") (class "Default")
      (node (ref "X3") (pin "R_96") (pinfunction "4DIO2_4_R_96") (pintype "passive"))
    )
    (net (code "164") (name "unconnected-(X3-4DIO2_5-PadR_98)") (class "Default")
      (node (ref "X3") (pin "R_98") (pinfunction "4DIO2_5_R_98") (pintype "passive"))
    )
    (net (code "165") (name "unconnected-(X3-4DIO2_6-PadR_100)") (class "Default")
      (node (ref "X3") (pin "R_100") (pinfunction "4DIO2_6_R_100") (pintype "passive"))
    )
    (net (code "166") (name "unconnected-(X3-4DIO2_7-PadR_99)") (class "Default")
      (node (ref "X3") (pin "R_99") (pinfunction "4DIO2_7_R_99") (pintype "passive"))
    )
    (net (code "167") (name "unconnected-(X3-A0+-PadR_48)") (class "Default")
      (node (ref "X3") (pin "R_48") (pinfunction "A0+_R_48") (pintype "passive"))
    )
    (net (code "168") (name "unconnected-(X3-A0--PadR_50)") (class "Default")
      (node (ref "X3") (pin "R_50") (pinfunction "A0-_R_50") (pintype "passive"))
    )
    (net (code "169") (name "unconnected-(X3-A1+-PadR_54)") (class "Default")
      (node (ref "X3") (pin "R_54") (pinfunction "A1+_R_54") (pintype "passive"))
    )
    (net (code "170") (name "unconnected-(X3-A1--PadR_52)") (class "Default")
      (node (ref "X3") (pin "R_52") (pinfunction "A1-_R_52") (pintype "passive"))
    )
    (net (code "171") (name "unconnected-(X4-0DIO_8-PadR_45)") (class "Default")
      (node (ref "X4") (pin "R_45") (pinfunction "0DIO_8_R_45") (pintype "passive"))
    )
    (net (code "172") (name "unconnected-(X4-0DIO_9-PadR_43)") (class "Default")
      (node (ref "X4") (pin "R_43") (pinfunction "0DIO_9_R_43") (pintype "passive"))
    )
    (net (code "173") (name "unconnected-(X4-0DIO_10-PadR_41)") (class "Default")
      (node (ref "X4") (pin "R_41") (pinfunction "0DIO_10_R_41") (pintype "passive"))
    )
    (net (code "174") (name "unconnected-(X4-0DIO_11-PadR_39)") (class "Default")
      (node (ref "X4") (pin "R_39") (pinfunction "0DIO_11_R_39") (pintype "passive"))
    )
    (net (code "175") (name "unconnected-(X4-0DIO_12-PadR_37)") (class "Default")
      (node (ref "X4") (pin "R_37") (pinfunction "0DIO_12_R_37") (pintype "passive"))
    )
    (net (code "176") (name "unconnected-(X4-0DIO_13-PadR_35)") (class "Default")
      (node (ref "X4") (pin "R_35") (pinfunction "0DIO_13_R_35") (pintype "passive"))
    )
    (net (code "177") (name "unconnected-(X4-2DIO_15-PadR_2)") (class "Default")
      (node (ref "X4") (pin "R_2") (pinfunction "2DIO_15_R_2") (pintype "passive"))
    )
    (net (code "178") (name "unconnected-(X4-2DIO_39-PadR_4)") (class "Default")
      (node (ref "X4") (pin "R_4") (pinfunction "2DIO_39_R_4") (pintype "passive"))
    )
    (net (code "179") (name "unconnected-(X4-3CLK_0-PadR_88)") (class "Default")
      (node (ref "X4") (pin "R_88") (pinfunction "3CLK_0_R_88") (pintype "passive"))
    )
    (net (code "180") (name "unconnected-(X4-3COUT-PadR_86)") (class "Default")
      (node (ref "X4") (pin "R_86") (pinfunction "3COUT_R_86") (pintype "passive"))
    )
    (net (code "181") (name "unconnected-(X4-3PFI_1-PadR_82)") (class "Default")
      (node (ref "X4") (pin "R_82") (pinfunction "3PFI_1_R_82") (pintype "passive"))
    )
    (net (code "182") (name "unconnected-(X4-3PFI_2-PadR_90)") (class "Default")
      (node (ref "X4") (pin "R_90") (pinfunction "3PFI_2_R_90") (pintype "passive"))
    )
    (net (code "183") (name "unconnected-(X4-3PFI_3-PadR_84)") (class "Default")
      (node (ref "X4") (pin "R_84") (pinfunction "3PFI_3_R_84") (pintype "passive"))
    )
    (net (code "184") (name "unconnected-(X4-4CLK_0-PadR_98)") (class "Default")
      (node (ref "X4") (pin "R_98") (pinfunction "4CLK_0_R_98") (pintype "passive"))
    )
    (net (code "185") (name "unconnected-(X4-4COUT-PadR_96)") (class "Default")
      (node (ref "X4") (pin "R_96") (pinfunction "4COUT_R_96") (pintype "passive"))
    )
    (net (code "186") (name "unconnected-(X4-4PFI_1-PadR_92)") (class "Default")
      (node (ref "X4") (pin "R_92") (pinfunction "4PFI_1_R_92") (pintype "passive"))
    )
    (net (code "187") (name "unconnected-(X4-4PFI_2-PadR_100)") (class "Default")
      (node (ref "X4") (pin "R_100") (pinfunction "4PFI_2_R_100") (pintype "passive"))
    )
    (net (code "188") (name "unconnected-(X4-4PFI_3-PadR_94)") (class "Default")
      (node (ref "X4") (pin "R_94") (pinfunction "4PFI_3_R_94") (pintype "passive"))
    )
    (net (code "189") (name "unconnected-(X4-A2+-PadR_51)") (class "Default")
      (node (ref "X4") (pin "R_51") (pinfunction "A2+_R_51") (pintype "passive"))
    )
    (net (code "190") (name "unconnected-(X4-A2--PadR_53)") (class "Default")
      (node (ref "X4") (pin "R_53") (pinfunction "A2-_R_53") (pintype "passive"))
    )
    (net (code "191") (name "unconnected-(X4-A3+-PadR_47)") (class "Default")
      (node (ref "X4") (pin "R_47") (pinfunction "A3+_R_47") (pintype "passive"))
    )
    (net (code "192") (name "unconnected-(X4-A3--PadR_49)") (class "Default")
      (node (ref "X4") (pin "R_49") (pinfunction "A3-_R_49") (pintype "passive"))
    )
    (net (code "193") (name "unconnected-(X4-AGND-PadR_63)") (class "Default")
      (node (ref "X4") (pin "R_63") (pinfunction "AGND_R_63") (pintype "passive"))
    )
    (net (code "194") (name "unconnected-(X4-AGND-PadR_69)") (class "Default")
      (node (ref "X4") (pin "R_69") (pinfunction "AGND_R_69") (pintype "passive"))
    )
    (net (code "195") (name "unconnected-(X4-AGND-PadR_75)") (class "Default")
      (node (ref "X4") (pin "R_75") (pinfunction "AGND_R_75") (pintype "passive"))
    )
    (net (code "196") (name "unconnected-(X4-AGND-PadR_81)") (class "Default")
      (node (ref "X4") (pin "R_81") (pinfunction "AGND_R_81") (pintype "passive"))
    )
    (net (code "197") (name "unconnected-(X4-AGND-PadR_85)") (class "Default")
      (node (ref "X4") (pin "R_85") (pinfunction "AGND_R_85") (pintype "passive"))
    )
    (net (code "198") (name "unconnected-(X4-AGND-PadR_87)") (class "Default")
      (node (ref "X4") (pin "R_87") (pinfunction "AGND_R_87") (pintype "passive"))
    )
    (net (code "199") (name "unconnected-(X4-AGND-PadR_89)") (class "Default")
      (node (ref "X4") (pin "R_89") (pinfunction "AGND_R_89") (pintype "passive"))
    )
    (net (code "200") (name "unconnected-(X4-AGND-PadR_91)") (class "Default")
      (node (ref "X4") (pin "R_91") (pinfunction "AGND_R_91") (pintype "passive"))
    )
    (net (code "201") (name "unconnected-(X4-AGND-PadR_93)") (class "Default")
      (node (ref "X4") (pin "R_93") (pinfunction "AGND_R_93") (pintype "passive"))
    )
    (net (code "202") (name "unconnected-(X4-AGND-PadR_95)") (class "Default")
      (node (ref "X4") (pin "R_95") (pinfunction "AGND_R_95") (pintype "passive"))
    )
    (net (code "203") (name "unconnected-(X4-AGND-PadR_97)") (class "Default")
      (node (ref "X4") (pin "R_97") (pinfunction "AGND_R_97") (pintype "passive"))
    )
    (net (code "204") (name "unconnected-(X4-AGND-PadR_99)") (class "Default")
      (node (ref "X4") (pin "R_99") (pinfunction "AGND_R_99") (pintype "passive"))
    )
    (net (code "205") (name "unconnected-(X4-AI4+-PadR_61)") (class "Default")
      (node (ref "X4") (pin "R_61") (pinfunction "AI4+_R_61") (pintype "passive"))
    )
    (net (code "206") (name "unconnected-(X4-AI4--PadR_59)") (class "Default")
      (node (ref "X4") (pin "R_59") (pinfunction "AI4-_R_59") (pintype "passive"))
    )
    (net (code "207") (name "unconnected-(X4-AI5+-PadR_67)") (class "Default")
      (node (ref "X4") (pin "R_67") (pinfunction "AI5+_R_67") (pintype "passive"))
    )
    (net (code "208") (name "unconnected-(X4-AI5--PadR_65)") (class "Default")
      (node (ref "X4") (pin "R_65") (pinfunction "AI5-_R_65") (pintype "passive"))
    )
    (net (code "209") (name "unconnected-(X4-AI6+-PadR_73)") (class "Default")
      (node (ref "X4") (pin "R_73") (pinfunction "AI6+_R_73") (pintype "passive"))
    )
    (net (code "210") (name "unconnected-(X4-AI6--PadR_71)") (class "Default")
      (node (ref "X4") (pin "R_71") (pinfunction "AI6-_R_71") (pintype "passive"))
    )
    (net (code "211") (name "unconnected-(X4-AI7+-PadR_79)") (class "Default")
      (node (ref "X4") (pin "R_79") (pinfunction "AI7+_R_79") (pintype "passive"))
    )
    (net (code "212") (name "unconnected-(X4-AI7--PadR_77)") (class "Default")
      (node (ref "X4") (pin "R_77") (pinfunction "AI7-_R_77") (pintype "passive"))
    )
    (net (code "213") (name "unconnected-(X4-AISENSE-PadR_83)") (class "Default")
      (node (ref "X4") (pin "R_83") (pinfunction "AISENSE_R_83") (pintype "passive"))
    )
    (net (code "214") (name "unconnected-(X4-DGND-PadR_52)") (class "Default")
      (node (ref "X4") (pin "R_52") (pinfunction "DGND_R_52") (pintype "passive"))
    )
    (net (code "215") (name "unconnected-(X4-DGND-PadR_54)") (class "Default")
      (node (ref "X4") (pin "R_54") (pinfunction "DGND_R_54") (pintype "passive"))
    )
    (net (code "216") (name "unconnected-(X4-DGND-PadR_56)") (class "Default")
      (node (ref "X4") (pin "R_56") (pinfunction "DGND_R_56") (pintype "passive"))
    )
    (net (code "217") (name "unconnected-(X4-DGND-PadR_58)") (class "Default")
      (node (ref "X4") (pin "R_58") (pinfunction "DGND_R_58") (pintype "passive"))
    )
    (net (code "218") (name "unconnected-(X4-DGND-PadR_60)") (class "Default")
      (node (ref "X4") (pin "R_60") (pinfunction "DGND_R_60") (pintype "passive"))
    )
    (net (code "219") (name "unconnected-(X4-DGND-PadR_62)") (class "Default")
      (node (ref "X4") (pin "R_62") (pinfunction "DGND_R_62") (pintype "passive"))
    )
    (net (code "220") (name "unconnected-(X4-DGND-PadR_78)") (class "Default")
      (node (ref "X4") (pin "R_78") (pinfunction "DGND_R_78") (pintype "passive"))
    )
    (net (code "221") (name "unconnected-(X4-DGND-PadR_80)") (class "Default")
      (node (ref "X4") (pin "R_80") (pinfunction "DGND_R_80") (pintype "passive"))
    )
    (net (code "222") (name "unconnected-(X4-DVCC12-PadR_66)") (class "Default")
      (node (ref "X4") (pin "R_66") (pinfunction "DVCC12_R_66") (pintype "passive"))
    )
    (net (code "223") (name "unconnected-(X4-DVCC12-PadR_68)") (class "Default")
      (node (ref "X4") (pin "R_68") (pinfunction "DVCC12_R_68") (pintype "passive"))
    )
    (net (code "224") (name "unconnected-(X4-DVCC13-PadR_70)") (class "Default")
      (node (ref "X4") (pin "R_70") (pinfunction "DVCC13_R_70") (pintype "passive"))
    )
    (net (code "225") (name "unconnected-(X4-DVCC13-PadR_72)") (class "Default")
      (node (ref "X4") (pin "R_72") (pinfunction "DVCC13_R_72") (pintype "passive"))
    )
    (net (code "226") (name "unconnected-(X4-NDVCC14-PadR_74)") (class "Default")
      (node (ref "X4") (pin "R_74") (pinfunction "NDVCC14_R_74") (pintype "passive"))
    )
    (net (code "227") (name "unconnected-(X4-NDVCC14-PadR_76)") (class "Default")
      (node (ref "X4") (pin "R_76") (pinfunction "NDVCC14_R_76") (pintype "passive"))
    )
    (net (code "228") (name "unconnected-(X4-PadR_55)") (class "Default")
      (node (ref "X4") (pin "R_55") (pinfunction "R_55_R_55") (pintype "passive"))
    )
    (net (code "229") (name "unconnected-(X4-PadR_57)") (class "Default")
      (node (ref "X4") (pin "R_57") (pinfunction "R_57_R_57") (pintype "passive"))
    )
    (net (code "230") (name "unconnected-(X4-PadR_64)") (class "Default")
      (node (ref "X4") (pin "R_64") (pinfunction "R_64_R_64") (pintype "passive"))
    )
  )
)
